# Grilo.net
KiCad netlist of a schematic drawn in EAGLE
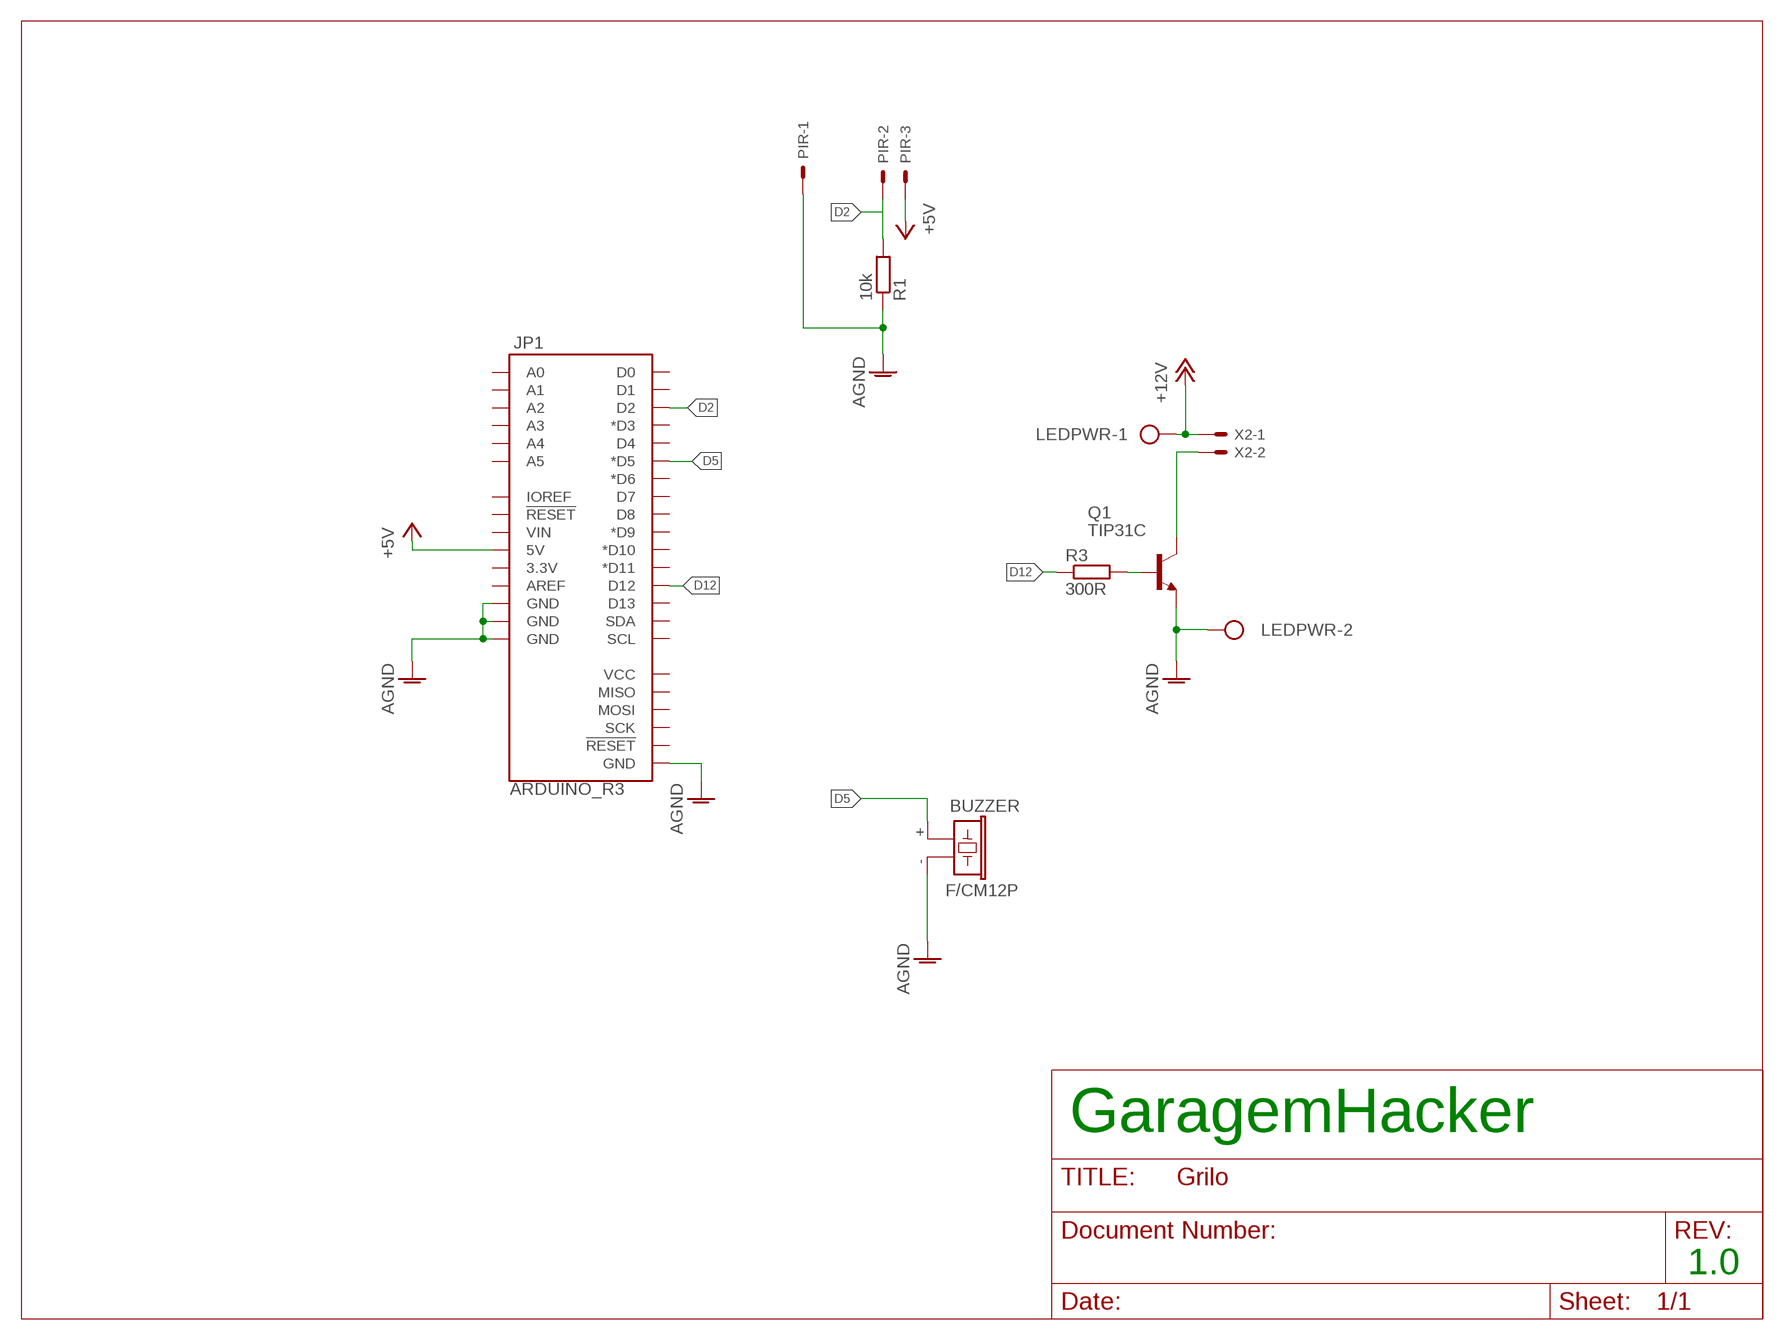
[diagram p0: schematic, sheet 1]

(export (version "E")
  (design (tool "Eeschema 10.0.6"))
  (components
    (comp (ref "BUZZER")
      (value "F/CM12P")
      (footprint "eagle-import:F_CM12P")
      (libsource (lib "eagle-import") (part "F/CM12P"))
    )
    (comp (ref "JP1")
      (value "ARDUINO_R3")
      (footprint "eagle-import:ARDUINO_R3")
      (libsource (lib "eagle-import") (part "ARDUINO_R3"))
    )
    (comp (ref "LEDPWR")
      (value "AK500/2")
      (footprint "eagle-import:AK500_2")
      (libsource (lib "eagle-import") (part "AK500/2"))
    )
    (comp (ref "PIR")
      (value "KK-156-3")
      (footprint "eagle-import:KK-156-3")
      (libsource (lib "eagle-import") (part "KK-156-3"))
    )
    (comp (ref "Q1")
      (value "TIP31C")
      (footprint "eagle-import:TO220V")
      (libsource (lib "eagle-import") (part "TIP31C"))
    )
    (comp (ref "R1")
      (value "10k")
      (footprint "eagle-import:0207_10")
      (libsource (lib "eagle-import") (part "R-EU_0207/10"))
    )
    (comp (ref "R3")
      (value "300R")
      (footprint "eagle-import:0207_10")
      (libsource (lib "eagle-import") (part "R-EU_0207/10"))
    )
    (comp (ref "X2")
      (value "KK-156-2")
      (footprint "eagle-import:KK-156-2")
      (libsource (lib "eagle-import") (part "KK-156-2"))
    )
  )
  (nets
    (net (code "1") (name "+5V") (class "Default")
      (node (ref "JP1") (pin "5V") (pinfunction "5V_5V") (pintype "bidirectional"))
      (node (ref "PIR") (pin "3") (pinfunction "S_3") (pintype "passive"))
    )
    (net (code "2") (name "+12V") (class "Default")
      (node (ref "LEDPWR") (pin "1") (pinfunction "KL_1") (pintype "passive"))
      (node (ref "X2") (pin "1") (pinfunction "S_1") (pintype "passive"))
    )
    (net (code "3") (name "AGND") (class "Default")
      (node (ref "BUZZER") (pin "-") (pinfunction "2_-") (pintype "passive"))
      (node (ref "JP1") (pin "GND@1") (pinfunction "GND_GND@1") (pintype "bidirectional"))
      (node (ref "JP1") (pin "GND@2") (pinfunction "GND_GND@2") (pintype "bidirectional"))
      (node (ref "JP1") (pin "GND@3") (pinfunction "GND_GND@3") (pintype "bidirectional"))
      (node (ref "JP1") (pin "GND@4") (pinfunction "GND_GND@4") (pintype "bidirectional"))
      (node (ref "LEDPWR") (pin "2") (pinfunction "KL_2") (pintype "passive"))
      (node (ref "PIR") (pin "1") (pinfunction "S_1") (pintype "passive"))
      (node (ref "Q1") (pin "3") (pinfunction "E_3") (pintype "passive"))
      (node (ref "R1") (pin "1") (pinfunction "1_1") (pintype "passive"))
    )
    (net (code "4") (name "D2") (class "Default")
      (node (ref "JP1") (pin "D2") (pinfunction "D2_D2") (pintype "bidirectional"))
      (node (ref "PIR") (pin "2") (pinfunction "S_2") (pintype "passive"))
      (node (ref "R1") (pin "2") (pinfunction "2_2") (pintype "passive"))
    )
    (net (code "5") (name "D5") (class "Default")
      (node (ref "BUZZER") (pin "+") (pinfunction "1_+") (pintype "passive"))
      (node (ref "JP1") (pin "D5") (pinfunction "*D5_D5") (pintype "bidirectional"))
    )
    (net (code "6") (name "D12") (class "Default")
      (node (ref "JP1") (pin "D12") (pinfunction "D12_D12") (pintype "bidirectional"))
      (node (ref "R3") (pin "1") (pinfunction "1_1") (pintype "passive"))
    )
    (net (code "7") (name "Net-(Q1-B)") (class "Default")
      (node (ref "Q1") (pin "1") (pinfunction "B_1") (pintype "passive"))
      (node (ref "R3") (pin "2") (pinfunction "2_2") (pintype "passive"))
    )
    (net (code "8") (name "Net-(Q1-C)") (class "Default")
      (node (ref "Q1") (pin "2") (pinfunction "C_2") (pintype "passive"))
      (node (ref "X2") (pin "2") (pinfunction "S_2") (pintype "passive"))
    )
    (net (code "9") (name "unconnected-(JP1-*D3-PadD3)") (class "Default")
      (node (ref "JP1") (pin "D3") (pinfunction "*D3_D3") (pintype "bidirectional"))
    )
    (net (code "10") (name "unconnected-(JP1-*D6-PadD6)") (class "Default")
      (node (ref "JP1") (pin "D6") (pinfunction "*D6_D6") (pintype "bidirectional"))
    )
    (net (code "11") (name "unconnected-(JP1-*D9-PadD9)") (class "Default")
      (node (ref "JP1") (pin "D9") (pinfunction "*D9_D9") (pintype "bidirectional"))
    )
    (net (code "12") (name "unconnected-(JP1-*D10-PadD10)") (class "Default")
      (node (ref "JP1") (pin "D10") (pinfunction "*D10_D10") (pintype "bidirectional"))
    )
    (net (code "13") (name "unconnected-(JP1-*D11-PadD11)") (class "Default")
      (node (ref "JP1") (pin "D11") (pinfunction "*D11_D11") (pintype "bidirectional"))
    )
    (net (code "14") (name "unconnected-(JP1-Pad3.3V)") (class "Default")
      (node (ref "JP1") (pin "3.3V") (pinfunction "3.3V_3.3V") (pintype "bidirectional"))
    )
    (net (code "15") (name "unconnected-(JP1-PadA0)") (class "Default")
      (node (ref "JP1") (pin "A0") (pinfunction "A0_A0") (pintype "bidirectional"))
    )
    (net (code "16") (name "unconnected-(JP1-PadA1)") (class "Default")
      (node (ref "JP1") (pin "A1") (pinfunction "A1_A1") (pintype "bidirectional"))
    )
    (net (code "17") (name "unconnected-(JP1-PadA2)") (class "Default")
      (node (ref "JP1") (pin "A2") (pinfunction "A2_A2") (pintype "bidirectional"))
    )
    (net (code "18") (name "unconnected-(JP1-PadA3)") (class "Default")
      (node (ref "JP1") (pin "A3") (pinfunction "A3_A3") (pintype "bidirectional"))
    )
    (net (code "19") (name "unconnected-(JP1-PadA4)") (class "Default")
      (node (ref "JP1") (pin "A4") (pinfunction "A4_A4") (pintype "bidirectional"))
    )
    (net (code "20") (name "unconnected-(JP1-PadA5)") (class "Default")
      (node (ref "JP1") (pin "A5") (pinfunction "A5_A5") (pintype "bidirectional"))
    )
    (net (code "21") (name "unconnected-(JP1-PadAREF)") (class "Default")
      (node (ref "JP1") (pin "AREF") (pinfunction "AREF_AREF") (pintype "bidirectional"))
    )
    (net (code "22") (name "unconnected-(JP1-PadD0)") (class "Default")
      (node (ref "JP1") (pin "D0") (pinfunction "D0_D0") (pintype "bidirectional"))
    )
    (net (code "23") (name "unconnected-(JP1-PadD1)") (class "Default")
      (node (ref "JP1") (pin "D1") (pinfunction "D1_D1") (pintype "bidirectional"))
    )
    (net (code "24") (name "unconnected-(JP1-PadD4)") (class "Default")
      (node (ref "JP1") (pin "D4") (pinfunction "D4_D4") (pintype "bidirectional"))
    )
    (net (code "25") (name "unconnected-(JP1-PadD7)") (class "Default")
      (node (ref "JP1") (pin "D7") (pinfunction "D7_D7") (pintype "bidirectional"))
    )
    (net (code "26") (name "unconnected-(JP1-PadD8)") (class "Default")
      (node (ref "JP1") (pin "D8") (pinfunction "D8_D8") (pintype "bidirectional"))
    )
    (net (code "27") (name "unconnected-(JP1-PadD13)") (class "Default")
      (node (ref "JP1") (pin "D13") (pinfunction "D13_D13") (pintype "bidirectional"))
    )
    (net (code "28") (name "unconnected-(JP1-PadIOREF)") (class "Default")
      (node (ref "JP1") (pin "IOREF") (pinfunction "IOREF_IOREF") (pintype "bidirectional"))
    )
    (net (code "29") (name "unconnected-(JP1-PadMISO)") (class "Default")
      (node (ref "JP1") (pin "MISO") (pinfunction "MISO_MISO") (pintype "bidirectional"))
    )
    (net (code "30") (name "unconnected-(JP1-PadMOSI)") (class "Default")
      (node (ref "JP1") (pin "MOSI") (pinfunction "MOSI_MOSI") (pintype "bidirectional"))
    )
    (net (code "31") (name "unconnected-(JP1-PadSCK)") (class "Default")
      (node (ref "JP1") (pin "SCK") (pinfunction "SCK_SCK") (pintype "bidirectional"))
    )
    (net (code "32") (name "unconnected-(JP1-PadSCL)") (class "Default")
      (node (ref "JP1") (pin "SCL") (pinfunction "SCL_SCL") (pintype "bidirectional"))
    )
    (net (code "33") (name "unconnected-(JP1-PadSDA)") (class "Default")
      (node (ref "JP1") (pin "SDA") (pinfunction "SDA_SDA") (pintype "bidirectional"))
    )
    (net (code "34") (name "unconnected-(JP1-PadVCC)") (class "Default")
      (node (ref "JP1") (pin "VCC") (pinfunction "VCC_VCC") (pintype "bidirectional"))
    )
    (net (code "35") (name "unconnected-(JP1-PadVIN)") (class "Default")
      (node (ref "JP1") (pin "VIN") (pinfunction "VIN_VIN") (pintype "bidirectional"))
    )
    (net (code "36") (name "unconnected-(JP1-~{RESET}-PadRESET@1)") (class "Default")
      (node (ref "JP1") (pin "RESET@1") (pinfunction "~{RESET}_RESET@1") (pintype "bidirectional"))
    )
    (net (code "37") (name "unconnected-(JP1-~{RESET}-PadRESET@2)") (class "Default")
      (node (ref "JP1") (pin "RESET@2") (pinfunction "~{RESET}_RESET@2") (pintype "bidirectional"))
    )
  )
)
